# Ambient_Light_Sensor.net
KiCad netlist of a schematic drawn in Altium Designer
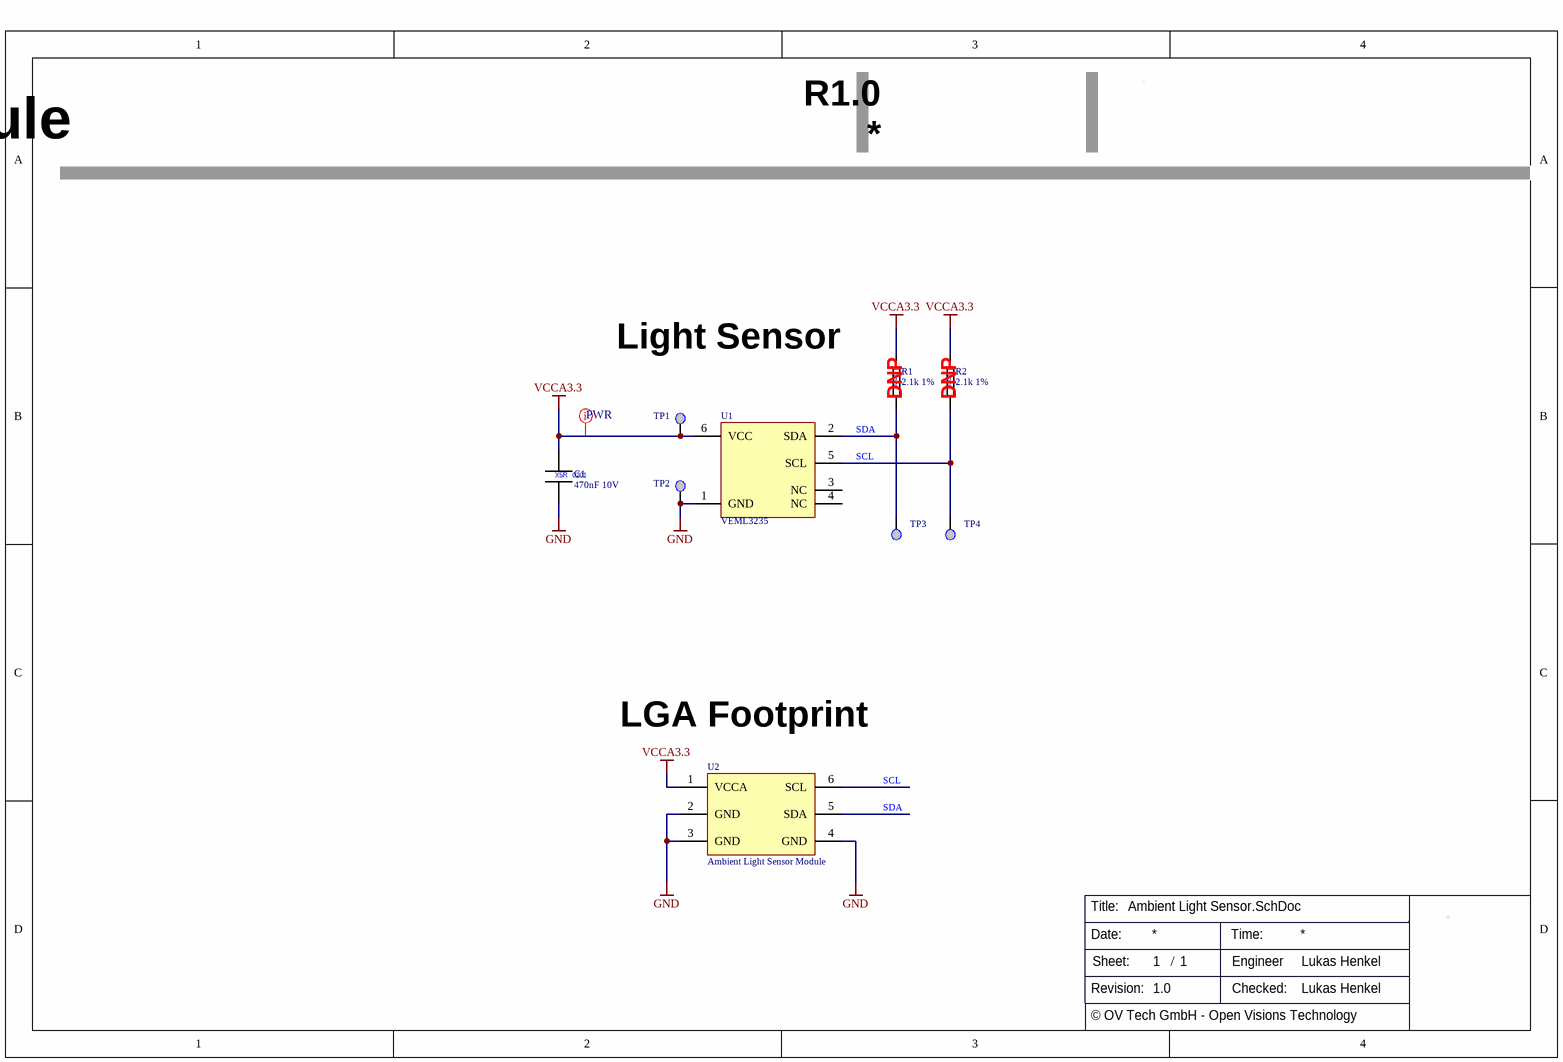
[diagram p0: Ambient Light Sensor.SchDoc]

(export (version "E")
  (design (tool "Eeschema 10.0.6"))
  (components
    (comp (ref "C1")
      (value "470nF 10V")
      (footprint "QV_Cap:CAPC0603X03L")
      (description "Multilayer Ceramic Capacitors MLCC - SMD/SMT 0201 10VDC")
      (libsource (lib "QV_Cap") (part "CAP_0201_470nF_10V"))
    )
    (comp (ref "R1")
      (value "2.1k 1%")
      (footprint "QV_Res:RESC0603X03L")
      (description "Thick Film Resistors - SMD 2.1K OHM 1%")
      (libsource (lib "QV_res") (part "RES_0201_2.1k_1%"))
    )
    (comp (ref "R2")
      (value "2.1k 1%")
      (footprint "QV_Res:RESC0603X03L")
      (description "Thick Film Resistors - SMD 2.1K OHM 1%")
      (libsource (lib "QV_res") (part "RES_0201_2.1k_1%"))
    )
    (comp (ref "TP1")
      (value "Testpoint 0.5mm")
      (footprint "QV_ElectroMech:TP_0.50mm")
      (libsource (lib "QV_ElectroMech") (part "Testpoint 0.5mm"))
    )
    (comp (ref "TP2")
      (value "Testpoint 0.5mm")
      (footprint "QV_ElectroMech:TP_0.50mm")
      (libsource (lib "QV_ElectroMech") (part "Testpoint 0.5mm"))
    )
    (comp (ref "TP3")
      (value "Testpoint 0.5mm")
      (footprint "QV_ElectroMech:TP_0.50mm")
      (libsource (lib "QV_ElectroMech") (part "Testpoint 0.5mm"))
    )
    (comp (ref "TP4")
      (value "Testpoint 0.5mm")
      (footprint "QV_ElectroMech:TP_0.50mm")
      (libsource (lib "QV_ElectroMech") (part "Testpoint 0.5mm"))
    )
    (comp (ref "U1")
      (value "VEML3235")
      (footprint "QV_Active:Light Sensor_VEML3235")
      (description "Ambient Light Sensors Low Power, High Sensitivity, I2C Ambient Light Sensor")
      (libsource (lib "QV_Active") (part "Ambient Light Sensor_VEML3235"))
    )
    (comp (ref "U2")
      (value "Ambient Light Sensor Module")
      (footprint "QV_ConMod:ABLS-R01-sensor-Module Footprint")
      (description "Custom PCB Ambient Light Sensor LGA Footprint")
      (libsource (lib "QV_ConMod") (part "ABLS-MOD-R01"))
    )
  )
  (nets
    (net (code "1") (name "/SCL") (class "Default")
      (node (ref "R2") (pin "1") (pinfunction "1_1") (pintype "passive"))
      (node (ref "TP4") (pin "TP") (pinfunction "TP_TP") (pintype "passive"))
      (node (ref "U1") (pin "5") (pinfunction "SCL_5") (pintype "passive"))
      (node (ref "U2") (pin "6") (pinfunction "SCL_6") (pintype "passive"))
    )
    (net (code "2") (name "/SDA") (class "Default")
      (node (ref "R1") (pin "1") (pinfunction "1_1") (pintype "passive"))
      (node (ref "TP3") (pin "TP") (pinfunction "TP_TP") (pintype "passive"))
      (node (ref "U1") (pin "2") (pinfunction "SDA_2") (pintype "passive"))
      (node (ref "U2") (pin "5") (pinfunction "SDA_5") (pintype "passive"))
    )
    (net (code "3") (name "GND") (class "Default")
      (node (ref "C1") (pin "2") (pinfunction "2_2") (pintype "passive"))
      (node (ref "TP2") (pin "TP") (pinfunction "TP_TP") (pintype "passive"))
      (node (ref "U1") (pin "1") (pinfunction "GND_1") (pintype "passive"))
      (node (ref "U2") (pin "2") (pinfunction "GND_2") (pintype "passive"))
      (node (ref "U2") (pin "3") (pinfunction "GND_3") (pintype "passive"))
      (node (ref "U2") (pin "4") (pinfunction "GND_4") (pintype "passive"))
    )
    (net (code "4") (name "VCCA3.3") (class "Default")
      (node (ref "C1") (pin "1") (pinfunction "1_1") (pintype "passive"))
      (node (ref "R1") (pin "2") (pinfunction "2_2") (pintype "passive"))
      (node (ref "R2") (pin "2") (pinfunction "2_2") (pintype "passive"))
      (node (ref "TP1") (pin "TP") (pinfunction "TP_TP") (pintype "passive"))
      (node (ref "U1") (pin "6") (pinfunction "VCC_6") (pintype "passive"))
      (node (ref "U2") (pin "1") (pinfunction "VCCA_1") (pintype "passive"))
    )
    (net (code "5") (name "unconnected-(U1-NC-Pad3)") (class "Default")
      (node (ref "U1") (pin "3") (pinfunction "NC_3") (pintype "passive"))
    )
    (net (code "6") (name "unconnected-(U1-NC-Pad4)") (class "Default")
      (node (ref "U1") (pin "4") (pinfunction "NC_4") (pintype "passive"))
    )
  )
)
